# SCH_ELLIE_BREAKOUTBOARD_ESP32S3.net
KiCad netlist of a schematic drawn in EasyEDA
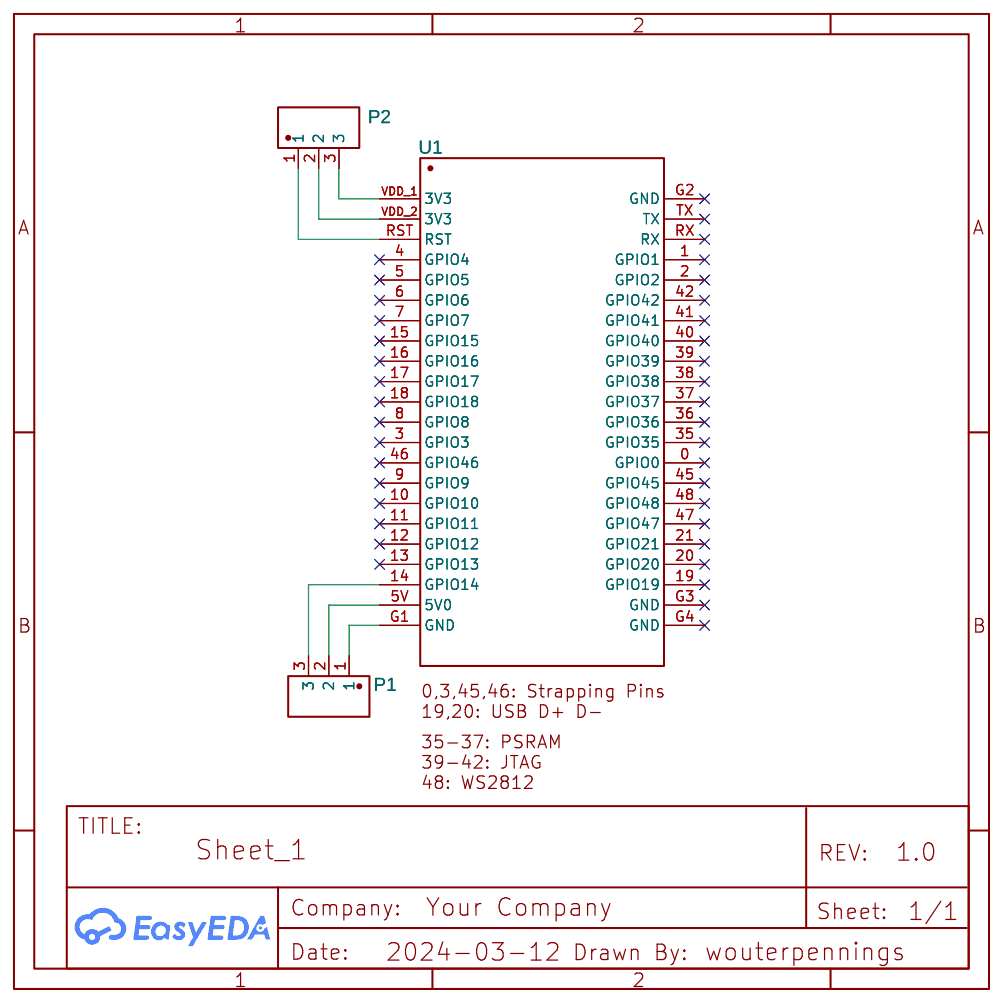
[diagram p0: schematic sheet]

(export (version "E")
  (design (tool "Eeschema 10.0.6"))
  (components
    (comp (ref "P1")
      (value "DB125-2.54-3P-GN")
      (fields
        (field (name "Manufacturer Part") "DB125-2.54-3P-GN-S")
        (field (name "Manufacturer") "DORABO(地博电气)")
      )
      (libsource (lib "") (part "DB125-2.54-3P-GN"))
    )
    (comp (ref "P2")
      (value "DB125-2.54-3P-GN")
      (fields
        (field (name "Manufacturer Part") "DB125-2.54-3P-GN-S")
        (field (name "Manufacturer") "DORABO(地博电气)")
      )
      (libsource (lib "") (part "DB125-2.54-3P-GN_1"))
    )
    (comp (ref "U1") (value "ESP32-S3-DEVKITC-MINI") (libsource (lib "") (part "ESP32-S3-DEVKITC-MINI")))
  )
  (nets
    (net (code "1") (name "Net-(P1-Pad1)") (class "Default")
      (node (ref "P1") (pin "1") (pinfunction "1_1") (pintype "unspecified"))
      (node (ref "U1") (pin "G1") (pinfunction "GND_G1") (pintype "bidirectional"))
    )
    (net (code "2") (name "Net-(P2-Pad1)") (class "Default")
      (node (ref "P2") (pin "1") (pinfunction "1_1") (pintype "unspecified"))
      (node (ref "U1") (pin "RST") (pinfunction "RST_RST") (pintype "bidirectional"))
    )
    (net (code "3") (name "Net-(P2-Pad2)") (class "Default")
      (node (ref "P2") (pin "2") (pinfunction "2_2") (pintype "unspecified"))
      (node (ref "U1") (pin "VDD_2") (pinfunction "3V3_VDD_2") (pintype "bidirectional"))
    )
    (net (code "4") (name "Net-(P2-Pad3)") (class "Default")
      (node (ref "P2") (pin "3") (pinfunction "3_3") (pintype "unspecified"))
      (node (ref "U1") (pin "VDD_1") (pinfunction "3V3_VDD_1") (pintype "bidirectional"))
    )
    (net (code "5") (name "Net-(U1-5V0)") (class "Default")
      (node (ref "P1") (pin "2") (pinfunction "2_2") (pintype "unspecified"))
      (node (ref "U1") (pin "5V") (pinfunction "5V0_5V") (pintype "bidirectional"))
    )
    (net (code "6") (name "Net-(U1-GPIO14)") (class "Default")
      (node (ref "P1") (pin "3") (pinfunction "3_3") (pintype "unspecified"))
      (node (ref "U1") (pin "14") (pinfunction "GPIO14_14") (pintype "bidirectional"))
    )
    (net (code "7") (name "unconnected-(U1-GND-PadG2)") (class "Default")
      (node (ref "U1") (pin "G2") (pinfunction "GND_G2") (pintype "bidirectional+no_connect"))
    )
    (net (code "8") (name "unconnected-(U1-GND-PadG3)") (class "Default")
      (node (ref "U1") (pin "G3") (pinfunction "GND_G3") (pintype "bidirectional+no_connect"))
    )
    (net (code "9") (name "unconnected-(U1-GND-PadG4)") (class "Default")
      (node (ref "U1") (pin "G4") (pinfunction "GND_G4") (pintype "bidirectional+no_connect"))
    )
    (net (code "10") (name "unconnected-(U1-GPIO0-Pad0)") (class "Default")
      (node (ref "U1") (pin "0") (pinfunction "GPIO0_0") (pintype "bidirectional+no_connect"))
    )
    (net (code "11") (name "unconnected-(U1-GPIO1-Pad1)") (class "Default")
      (node (ref "U1") (pin "1") (pinfunction "GPIO1_1") (pintype "bidirectional+no_connect"))
    )
    (net (code "12") (name "unconnected-(U1-GPIO2-Pad2)") (class "Default")
      (node (ref "U1") (pin "2") (pinfunction "GPIO2_2") (pintype "bidirectional+no_connect"))
    )
    (net (code "13") (name "unconnected-(U1-GPIO3-Pad3)") (class "Default")
      (node (ref "U1") (pin "3") (pinfunction "GPIO3_3") (pintype "bidirectional+no_connect"))
    )
    (net (code "14") (name "unconnected-(U1-GPIO4-Pad4)") (class "Default")
      (node (ref "U1") (pin "4") (pinfunction "GPIO4_4") (pintype "bidirectional+no_connect"))
    )
    (net (code "15") (name "unconnected-(U1-GPIO5-Pad5)") (class "Default")
      (node (ref "U1") (pin "5") (pinfunction "GPIO5_5") (pintype "bidirectional+no_connect"))
    )
    (net (code "16") (name "unconnected-(U1-GPIO6-Pad6)") (class "Default")
      (node (ref "U1") (pin "6") (pinfunction "GPIO6_6") (pintype "bidirectional+no_connect"))
    )
    (net (code "17") (name "unconnected-(U1-GPIO7-Pad7)") (class "Default")
      (node (ref "U1") (pin "7") (pinfunction "GPIO7_7") (pintype "bidirectional+no_connect"))
    )
    (net (code "18") (name "unconnected-(U1-GPIO8-Pad8)") (class "Default")
      (node (ref "U1") (pin "8") (pinfunction "GPIO8_8") (pintype "bidirectional+no_connect"))
    )
    (net (code "19") (name "unconnected-(U1-GPIO9-Pad9)") (class "Default")
      (node (ref "U1") (pin "9") (pinfunction "GPIO9_9") (pintype "bidirectional+no_connect"))
    )
    (net (code "20") (name "unconnected-(U1-GPIO10-Pad10)") (class "Default")
      (node (ref "U1") (pin "10") (pinfunction "GPIO10_10") (pintype "bidirectional+no_connect"))
    )
    (net (code "21") (name "unconnected-(U1-GPIO11-Pad11)") (class "Default")
      (node (ref "U1") (pin "11") (pinfunction "GPIO11_11") (pintype "bidirectional+no_connect"))
    )
    (net (code "22") (name "unconnected-(U1-GPIO12-Pad12)") (class "Default")
      (node (ref "U1") (pin "12") (pinfunction "GPIO12_12") (pintype "bidirectional+no_connect"))
    )
    (net (code "23") (name "unconnected-(U1-GPIO13-Pad13)") (class "Default")
      (node (ref "U1") (pin "13") (pinfunction "GPIO13_13") (pintype "bidirectional+no_connect"))
    )
    (net (code "24") (name "unconnected-(U1-GPIO15-Pad15)") (class "Default")
      (node (ref "U1") (pin "15") (pinfunction "GPIO15_15") (pintype "bidirectional+no_connect"))
    )
    (net (code "25") (name "unconnected-(U1-GPIO16-Pad16)") (class "Default")
      (node (ref "U1") (pin "16") (pinfunction "GPIO16_16") (pintype "bidirectional+no_connect"))
    )
    (net (code "26") (name "unconnected-(U1-GPIO17-Pad17)") (class "Default")
      (node (ref "U1") (pin "17") (pinfunction "GPIO17_17") (pintype "bidirectional+no_connect"))
    )
    (net (code "27") (name "unconnected-(U1-GPIO18-Pad18)") (class "Default")
      (node (ref "U1") (pin "18") (pinfunction "GPIO18_18") (pintype "bidirectional+no_connect"))
    )
    (net (code "28") (name "unconnected-(U1-GPIO19-Pad19)") (class "Default")
      (node (ref "U1") (pin "19") (pinfunction "GPIO19_19") (pintype "bidirectional+no_connect"))
    )
    (net (code "29") (name "unconnected-(U1-GPIO20-Pad20)") (class "Default")
      (node (ref "U1") (pin "20") (pinfunction "GPIO20_20") (pintype "bidirectional+no_connect"))
    )
    (net (code "30") (name "unconnected-(U1-GPIO21-Pad21)") (class "Default")
      (node (ref "U1") (pin "21") (pinfunction "GPIO21_21") (pintype "bidirectional+no_connect"))
    )
    (net (code "31") (name "unconnected-(U1-GPIO35-Pad35)") (class "Default")
      (node (ref "U1") (pin "35") (pinfunction "GPIO35_35") (pintype "bidirectional+no_connect"))
    )
    (net (code "32") (name "unconnected-(U1-GPIO36-Pad36)") (class "Default")
      (node (ref "U1") (pin "36") (pinfunction "GPIO36_36") (pintype "bidirectional+no_connect"))
    )
    (net (code "33") (name "unconnected-(U1-GPIO37-Pad37)") (class "Default")
      (node (ref "U1") (pin "37") (pinfunction "GPIO37_37") (pintype "bidirectional+no_connect"))
    )
    (net (code "34") (name "unconnected-(U1-GPIO38-Pad38)") (class "Default")
      (node (ref "U1") (pin "38") (pinfunction "GPIO38_38") (pintype "bidirectional+no_connect"))
    )
    (net (code "35") (name "unconnected-(U1-GPIO39-Pad39)") (class "Default")
      (node (ref "U1") (pin "39") (pinfunction "GPIO39_39") (pintype "bidirectional+no_connect"))
    )
    (net (code "36") (name "unconnected-(U1-GPIO40-Pad40)") (class "Default")
      (node (ref "U1") (pin "40") (pinfunction "GPIO40_40") (pintype "bidirectional+no_connect"))
    )
    (net (code "37") (name "unconnected-(U1-GPIO41-Pad41)") (class "Default")
      (node (ref "U1") (pin "41") (pinfunction "GPIO41_41") (pintype "bidirectional+no_connect"))
    )
    (net (code "38") (name "unconnected-(U1-GPIO42-Pad42)") (class "Default")
      (node (ref "U1") (pin "42") (pinfunction "GPIO42_42") (pintype "bidirectional+no_connect"))
    )
    (net (code "39") (name "unconnected-(U1-GPIO45-Pad45)") (class "Default")
      (node (ref "U1") (pin "45") (pinfunction "GPIO45_45") (pintype "bidirectional+no_connect"))
    )
    (net (code "40") (name "unconnected-(U1-GPIO46-Pad46)") (class "Default")
      (node (ref "U1") (pin "46") (pinfunction "GPIO46_46") (pintype "bidirectional+no_connect"))
    )
    (net (code "41") (name "unconnected-(U1-GPIO47-Pad47)") (class "Default")
      (node (ref "U1") (pin "47") (pinfunction "GPIO47_47") (pintype "bidirectional+no_connect"))
    )
    (net (code "42") (name "unconnected-(U1-GPIO48-Pad48)") (class "Default")
      (node (ref "U1") (pin "48") (pinfunction "GPIO48_48") (pintype "bidirectional+no_connect"))
    )
    (net (code "43") (name "unconnected-(U1-PadRX)") (class "Default")
      (node (ref "U1") (pin "RX") (pinfunction "RX_RX") (pintype "bidirectional+no_connect"))
    )
    (net (code "44") (name "unconnected-(U1-PadTX)") (class "Default")
      (node (ref "U1") (pin "TX") (pinfunction "TX_TX") (pintype "bidirectional+no_connect"))
    )
  )
)
